# Pyro.net
KiCad netlist of a schematic drawn in Altium Designer
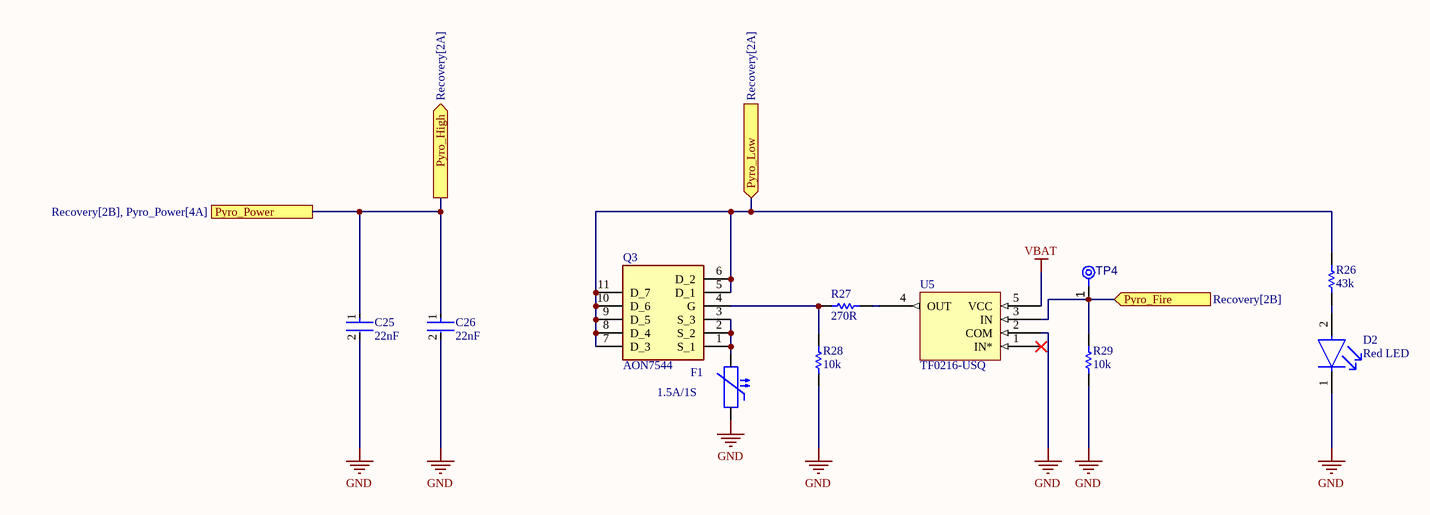
[diagram p0: Pyro.SchDoc]

(export (version "E")
  (design (tool "Eeschema 10.0.6"))
  (components
    (comp (ref "C25")
      (value "22nF")
      (footprint "FP-0603-L_1_6_0_15-W_0_81-IPC_C")
      (description "Generic 0603 Capacitor")
      (fields (field (name "LCSC PART #") "C21122") (field (name "TOLERANCE") "10%"))
      (libsource (lib "StrathSEDS") (part "02cd4be3c70576c341d710602a673aa"))
    )
    (comp (ref "C26")
      (value "22nF")
      (footprint "FP-0603-L_1_6_0_15-W_0_81-IPC_C")
      (description "Generic 0603 Capacitor")
      (fields (field (name "LCSC PART #") "C21122") (field (name "TOLERANCE") "10%"))
      (libsource (lib "StrathSEDS") (part "02cd4be3c70576c341d710602a673aa"))
    )
    (comp (ref "D2")
      (value "Red LED")
      (footprint "FP-LTST-C190GKT-MFG")
      (description "SZYY0603R")
      (fields (field (name "LCSC PART #") "C434419"))
      (libsource (lib "StrathSEDS Mach 22") (part "8706943c75ba83719d021d2fdc84c58"))
    )
    (comp (ref "F1")
      (value "1.5A/1S")
      (footprint "RESC3115X65N")
      (description "Polymeric PTC Resettable Fuse 30V 0.75A Surface Mount 1206")
      (libsource (lib "Other") (part "ASMD1206-075-30V"))
    )
    (comp (ref "Q3")
      (value "AON7544")
      (footprint "AON7544")
      (description "MOSFET N Trench 30V 30A(Tc) 2.2V @ 250uA 5 m @ 20A,10V DFN-8_3x3 EP RoHS")
      (fields (field (name "LCSC PART #") "C315567"))
      (libsource (lib "StrathSEDS") (part "AON7544"))
    )
    (comp (ref "R26")
      (value "43k")
      (footprint "RESC1609X50X30ML8T20")
      (description "Generic 0603 Resistor")
      (fields (field (name "TOLERANCE") "0%") (field (name "LCSC PART #") "C23172"))
      (libsource (lib "StrathSEDS") (part "RES-2"))
    )
    (comp (ref "R27")
      (value "270R")
      (footprint "RESC1609X50X30ML8T20")
      (description "Generic 0603 Resistor")
      (fields (field (name "TOLERANCE") "0%") (field (name "LCSC PART #") "C22966"))
      (libsource (lib "StrathSEDS") (part "RES-2"))
    )
    (comp (ref "R28")
      (value "10k")
      (footprint "RESC1609X50X30ML8T20")
      (description "Generic 0603 Resistor")
      (fields (field (name "TOLERANCE") "0%") (field (name "LCSC PART #") "C25804"))
      (libsource (lib "StrathSEDS") (part "RES-2"))
    )
    (comp (ref "R29")
      (value "10k")
      (footprint "RESC1609X50X30ML8T20")
      (description "Generic 0603 Resistor")
      (fields (field (name "TOLERANCE") "0%") (field (name "LCSC PART #") "C25804"))
      (libsource (lib "StrathSEDS") (part "RES-2"))
    )
    (comp (ref "TP4")
      (value "TPAD6R")
      (footprint "TP06R")
      (description "0.6mm round")
      (libsource (lib "StrathSEDS") (part "CMP-001-0001-4"))
    )
    (comp (ref "U5")
      (value "TF0216-USQ")
      (footprint "SOT95P245X110-5N")
      (description "High Speed, Low-Side, Single Gate Driver")
      (fields (field (name "LCSC PART #") "C2683769"))
      (libsource (lib "StrathSEDS") (part "TF0216-USQ"))
    )
  )
  (nets
    (net (code "1") (name "/Pyro_Fire") (class "Default")
      (node (ref "R29") (pin "2") (pinfunction "2_2") (pintype "passive"))
      (node (ref "TP4") (pin "1") (pinfunction "TP_1") (pintype "passive"))
      (node (ref "U5") (pin "3") (pinfunction "IN_3") (pintype "input"))
    )
    (net (code "2") (name "/Pyro_High") (class "Default")
      (node (ref "C25") (pin "1") (pinfunction "1_1") (pintype "passive"))
      (node (ref "C26") (pin "1") (pinfunction "1_1") (pintype "passive"))
    )
    (net (code "3") (name "/Pyro_Low") (class "Default")
      (node (ref "Q3") (pin "10") (pinfunction "D_6_10") (pintype "passive"))
      (node (ref "Q3") (pin "11") (pinfunction "D_7_11") (pintype "passive"))
      (node (ref "Q3") (pin "5") (pinfunction "D_1_5") (pintype "passive"))
      (node (ref "Q3") (pin "6") (pinfunction "D_2_6") (pintype "passive"))
      (node (ref "Q3") (pin "7") (pinfunction "D_3_7") (pintype "passive"))
      (node (ref "Q3") (pin "8") (pinfunction "D_4_8") (pintype "passive"))
      (node (ref "Q3") (pin "9") (pinfunction "D_5_9") (pintype "passive"))
      (node (ref "R26") (pin "2") (pinfunction "2_2") (pintype "passive"))
    )
    (net (code "4") (name "GND") (class "Default")
      (node (ref "C25") (pin "2") (pinfunction "2_2") (pintype "passive"))
      (node (ref "C26") (pin "2") (pinfunction "2_2") (pintype "passive"))
      (node (ref "D2") (pin "1") (pinfunction "C_1") (pintype "passive"))
      (node (ref "F1") (pin "2") (pinfunction "2_2") (pintype "passive"))
      (node (ref "R28") (pin "1") (pinfunction "1_1") (pintype "passive"))
      (node (ref "R29") (pin "1") (pinfunction "1_1") (pintype "passive"))
      (node (ref "U5") (pin "2") (pinfunction "COM_2") (pintype "input"))
    )
    (net (code "5") (name "Net-(D2-A)") (class "Default")
      (node (ref "D2") (pin "2") (pinfunction "A_2") (pintype "passive"))
      (node (ref "R26") (pin "1") (pinfunction "1_1") (pintype "passive"))
    )
    (net (code "6") (name "Net-(Q3-G)") (class "Default")
      (node (ref "Q3") (pin "4") (pinfunction "G_4") (pintype "passive"))
      (node (ref "R27") (pin "1") (pinfunction "1_1") (pintype "passive"))
      (node (ref "R28") (pin "2") (pinfunction "2_2") (pintype "passive"))
    )
    (net (code "7") (name "Net-(Q3-S_1)") (class "Default")
      (node (ref "F1") (pin "1") (pinfunction "1_1") (pintype "passive"))
      (node (ref "Q3") (pin "1") (pinfunction "S_1_1") (pintype "passive"))
      (node (ref "Q3") (pin "2") (pinfunction "S_2_2") (pintype "passive"))
      (node (ref "Q3") (pin "3") (pinfunction "S_3_3") (pintype "passive"))
    )
    (net (code "8") (name "Net-(U5-OUT)") (class "Default")
      (node (ref "R27") (pin "2") (pinfunction "2_2") (pintype "passive"))
      (node (ref "U5") (pin "4") (pinfunction "OUT_4") (pintype "output"))
    )
    (net (code "9") (name "VBAT") (class "Default")
      (node (ref "U5") (pin "5") (pinfunction "VCC_5") (pintype "input"))
    )
    (net (code "10") (name "unconnected-(U5-IN*-Pad1)") (class "Default")
      (node (ref "U5") (pin "1") (pinfunction "IN*_1") (pintype "input+no_connect"))
    )
  )
)
